# HDR_camera_controller.net
KiCad netlist of a schematic drawn in EAGLE
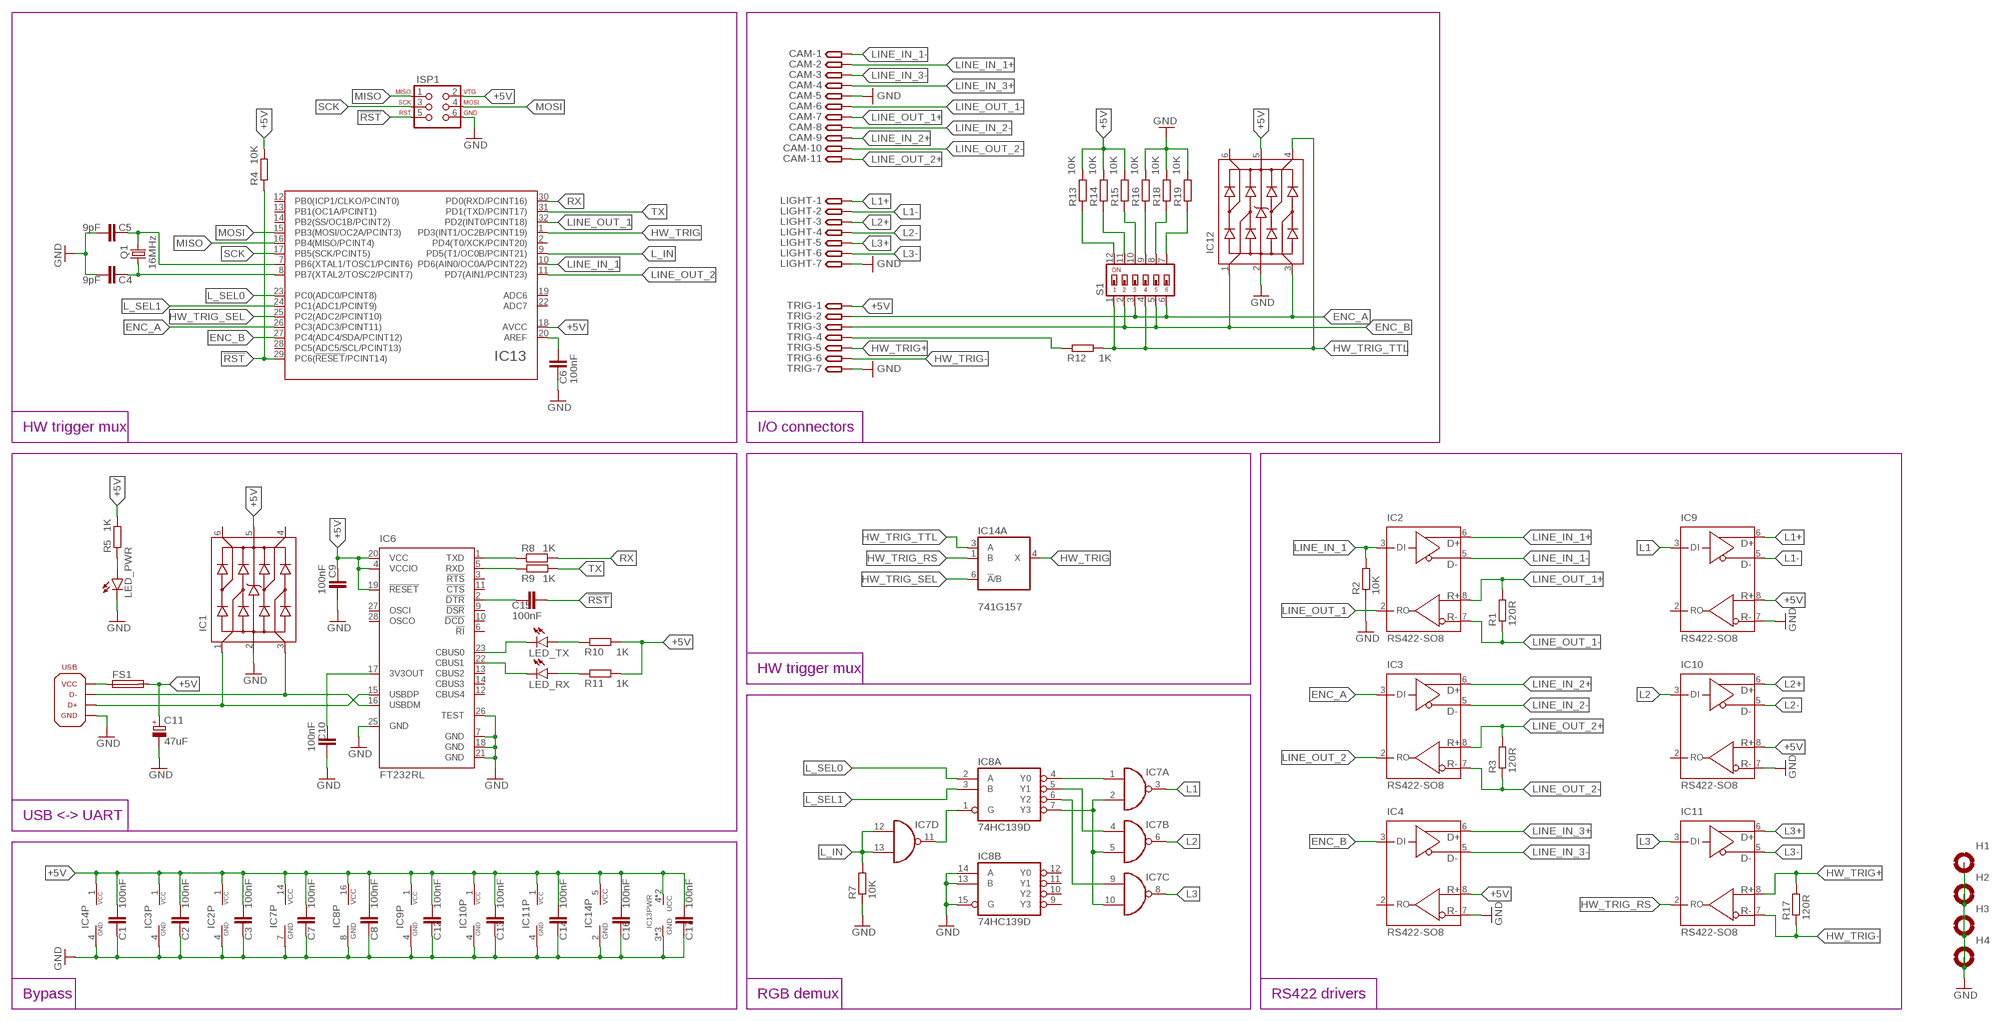
[diagram p0: schematic, sheet 1]

(export (version "E")
  (design (tool "Eeschema 10.0.6"))
  (components
    (comp (ref "C1")
      (value "100nF")
      (footprint "eagle-import:C0805")
      (libsource (lib "eagle-import") (part "C-EUC0805"))
    )
    (comp (ref "C2")
      (value "100nF")
      (footprint "eagle-import:C0805")
      (libsource (lib "eagle-import") (part "C-EUC0805"))
    )
    (comp (ref "C3")
      (value "100nF")
      (footprint "eagle-import:C0805")
      (libsource (lib "eagle-import") (part "C-EUC0805"))
    )
    (comp (ref "C4")
      (value "9pF")
      (footprint "eagle-import:C0805")
      (libsource (lib "eagle-import") (part "C-EUC0805"))
    )
    (comp (ref "C5")
      (value "9pF")
      (footprint "eagle-import:C0805")
      (libsource (lib "eagle-import") (part "C-EUC0805"))
    )
    (comp (ref "C6")
      (value "100nF")
      (footprint "eagle-import:C0805")
      (libsource (lib "eagle-import") (part "C-EUC0805"))
    )
    (comp (ref "C7")
      (value "100nF")
      (footprint "eagle-import:C0805")
      (libsource (lib "eagle-import") (part "C-EUC0805"))
    )
    (comp (ref "C8")
      (value "100nF")
      (footprint "eagle-import:C0805")
      (libsource (lib "eagle-import") (part "C-EUC0805"))
    )
    (comp (ref "C9")
      (value "100nF")
      (footprint "eagle-import:C0805")
      (libsource (lib "eagle-import") (part "C-EUC0805"))
    )
    (comp (ref "C10")
      (value "100nF")
      (footprint "eagle-import:C0805")
      (libsource (lib "eagle-import") (part "C-EUC0805"))
    )
    (comp (ref "C11")
      (value "47uF")
      (footprint "eagle-import:153CLV-0605")
      (fields (field (name "MPN") "SC1E476M6L005VR"))
      (libsource (lib "eagle-import") (part "CPOL-EU153CLV-0605"))
    )
    (comp (ref "C12")
      (value "100nF")
      (footprint "eagle-import:C0805")
      (libsource (lib "eagle-import") (part "C-EUC0805"))
    )
    (comp (ref "C13")
      (value "100nF")
      (footprint "eagle-import:C0805")
      (libsource (lib "eagle-import") (part "C-EUC0805"))
    )
    (comp (ref "C14")
      (value "100nF")
      (footprint "eagle-import:C0805")
      (libsource (lib "eagle-import") (part "C-EUC0805"))
    )
    (comp (ref "C15")
      (value "100nF")
      (footprint "eagle-import:C0805")
      (libsource (lib "eagle-import") (part "C-EUC0805"))
    )
    (comp (ref "C16")
      (value "100nF")
      (footprint "eagle-import:C0805")
      (libsource (lib "eagle-import") (part "C-EUC0805"))
    )
    (comp (ref "C17")
      (value "100nF")
      (footprint "eagle-import:C0805")
      (libsource (lib "eagle-import") (part "C-EUC0805"))
    )
    (comp (ref "CAM")
      (value "SMPAD-11")
      (footprint "eagle-import:S-11P")
      (libsource (lib "eagle-import") (part "SMPAD-11"))
    )
    (comp (ref "FS1")
      (value "POLYFUSE_1210")
      (footprint "eagle-import:1210")
      (fields (field (name "MPN") "SM010-60"))
      (libsource (lib "eagle-import") (part "POLYFUSE_1210"))
    )
    (comp (ref "H1")
      (value "HOLE-3MM_PLATED")
      (footprint "eagle-import:3MM_PLATED")
      (libsource (lib "eagle-import") (part "HOLE-3MM_PLATED"))
    )
    (comp (ref "H2")
      (value "HOLE-3MM_PLATED")
      (footprint "eagle-import:3MM_PLATED")
      (libsource (lib "eagle-import") (part "HOLE-3MM_PLATED"))
    )
    (comp (ref "H3")
      (value "HOLE-3MM_PLATED")
      (footprint "eagle-import:3MM_PLATED")
      (libsource (lib "eagle-import") (part "HOLE-3MM_PLATED"))
    )
    (comp (ref "H4")
      (value "HOLE-3MM_PLATED")
      (footprint "eagle-import:3MM_PLATED")
      (libsource (lib "eagle-import") (part "HOLE-3MM_PLATED"))
    )
    (comp (ref "IC1")
      (value "USBLC6-4")
      (footprint "eagle-import:SOT23-6")
      (fields (field (name "MPN") "USBLC6"))
      (libsource (lib "eagle-import") (part "USBLC6-4"))
    )
    (comp (ref "IC2")
      (value "RS422-SO8")
      (footprint "eagle-import:SO08")
      (fields
        (field (name "MF") "MAXIM")
        (field (name "MPN") "MAX488CSA")
        (field (name "MPN_1") "DS8921AMX/NOPB")
      )
      (libsource (lib "eagle-import") (part "RS422-SO8"))
    )
    (comp (ref "IC3")
      (value "RS422-SO8")
      (footprint "eagle-import:SO08")
      (fields
        (field (name "MF") "MAXIM")
        (field (name "MPN") "MAX488CSA")
        (field (name "MPN_1") "DS8921AMX/NOPB")
      )
      (libsource (lib "eagle-import") (part "RS422-SO8"))
    )
    (comp (ref "IC4")
      (value "RS422-SO8")
      (footprint "eagle-import:SO08")
      (fields
        (field (name "MF") "MAXIM")
        (field (name "MPN") "MAX488CSA")
        (field (name "MPN_1") "DS8921AMX/NOPB")
      )
      (libsource (lib "eagle-import") (part "RS422-SO8"))
    )
    (comp (ref "IC6")
      (value "FT232RL")
      (footprint "eagle-import:SSOP28")
      (libsource (lib "eagle-import") (part "FT232RL"))
    )
    (comp (ref "IC7")
      (value "74HC00D")
      (footprint "eagle-import:SO14")
      (fields (field (name "MPN") "SN74HC00DR"))
      (libsource (lib "eagle-import") (part "7400DHC"))
    )
    (comp (ref "IC8")
      (value "74HC139D")
      (footprint "eagle-import:SO16")
      (fields (field (name "MPN") "SN74HC139DR"))
      (libsource (lib "eagle-import") (part "74139DHC"))
    )
    (comp (ref "IC9")
      (value "RS422-SO8")
      (footprint "eagle-import:SO08")
      (fields
        (field (name "MF") "MAXIM")
        (field (name "MPN") "MAX488CSA")
        (field (name "MPN_1") "DS8921AMX/NOPB")
      )
      (libsource (lib "eagle-import") (part "RS422-SO8"))
    )
    (comp (ref "IC10")
      (value "RS422-SO8")
      (footprint "eagle-import:SO08")
      (fields
        (field (name "MF") "MAXIM")
        (field (name "MPN") "MAX488CSA")
        (field (name "MPN_1") "DS8921AMX/NOPB")
      )
      (libsource (lib "eagle-import") (part "RS422-SO8"))
    )
    (comp (ref "IC11")
      (value "RS422-SO8")
      (footprint "eagle-import:SO08")
      (fields
        (field (name "MF") "MAXIM")
        (field (name "MPN") "MAX488CSA")
        (field (name "MPN_1") "DS8921AMX/NOPB")
      )
      (libsource (lib "eagle-import") (part "RS422-SO8"))
    )
    (comp (ref "IC12")
      (value "USBLC6-4")
      (footprint "eagle-import:SOT23-6")
      (fields (field (name "MPN") "USBLC6"))
      (libsource (lib "eagle-import") (part "USBLC6-4"))
    )
    (comp (ref "IC13")
      (value "ATMEGA48/88/168/328-AU")
      (footprint "eagle-import:TQFP32-08")
      (libsource (lib "eagle-import") (part "ATMEGA48/88/168/328-AU"))
    )
    (comp (ref "IC14")
      (value "741G157")
      (footprint "eagle-import:SOT457W_PHILIPS")
      (fields (field (name "MPN") "74LVC1G157GV.125"))
      (libsource (lib "eagle-import") (part "741G157"))
    )
    (comp (ref "ISP1")
      (value "ISP-SMD")
      (footprint "eagle-import:ISP_SMD")
      (libsource (lib "eagle-import") (part "ISP-SMD"))
    )
    (comp (ref "LED_PWR")
      (value "LEDSML0805")
      (footprint "eagle-import:SML0805")
      (libsource (lib "eagle-import") (part "LEDSML0805"))
    )
    (comp (ref "LED_RX")
      (value "LEDSML0805")
      (footprint "eagle-import:SML0805")
      (libsource (lib "eagle-import") (part "LEDSML0805"))
    )
    (comp (ref "LED_TX")
      (value "LEDSML0805")
      (footprint "eagle-import:SML0805")
      (libsource (lib "eagle-import") (part "LEDSML0805"))
    )
    (comp (ref "LIGHT")
      (value "SMPAD-7")
      (footprint "eagle-import:S-7P")
      (libsource (lib "eagle-import") (part "SMPAD-7"))
    )
    (comp (ref "Q1")
      (value "16MHz")
      (footprint "eagle-import:CRYSTAL-3.2X2.5")
      (fields (field (name "MPN") "3225-16M-SR"))
      (libsource (lib "eagle-import") (part "RESONATOR_CRY"))
    )
    (comp (ref "R1")
      (value "120R")
      (footprint "eagle-import:R0805")
      (libsource (lib "eagle-import") (part "R-EU_R0805"))
    )
    (comp (ref "R2")
      (value "10K")
      (footprint "eagle-import:R0805")
      (libsource (lib "eagle-import") (part "R-EU_R0805"))
    )
    (comp (ref "R3")
      (value "120R")
      (footprint "eagle-import:R0805")
      (libsource (lib "eagle-import") (part "R-EU_R0805"))
    )
    (comp (ref "R4")
      (value "10K")
      (footprint "eagle-import:R0805")
      (libsource (lib "eagle-import") (part "R-EU_R0805"))
    )
    (comp (ref "R5")
      (value "1K")
      (footprint "eagle-import:R0805")
      (libsource (lib "eagle-import") (part "R-EU_R0805"))
    )
    (comp (ref "R7")
      (value "10K")
      (footprint "eagle-import:R0805")
      (libsource (lib "eagle-import") (part "R-EU_R0805"))
    )
    (comp (ref "R8")
      (value "1K")
      (footprint "eagle-import:R0805")
      (libsource (lib "eagle-import") (part "R-EU_R0805"))
    )
    (comp (ref "R9")
      (value "1K")
      (footprint "eagle-import:R0805")
      (libsource (lib "eagle-import") (part "R-EU_R0805"))
    )
    (comp (ref "R10")
      (value "1K")
      (footprint "eagle-import:R0805")
      (libsource (lib "eagle-import") (part "R-EU_R0805"))
    )
    (comp (ref "R11")
      (value "1K")
      (footprint "eagle-import:R0805")
      (libsource (lib "eagle-import") (part "R-EU_R0805"))
    )
    (comp (ref "R12")
      (value "1K")
      (footprint "eagle-import:R0805")
      (libsource (lib "eagle-import") (part "R-EU_R0805"))
    )
    (comp (ref "R13")
      (value "10K")
      (footprint "eagle-import:R0805")
      (libsource (lib "eagle-import") (part "R-EU_R0805"))
    )
    (comp (ref "R14")
      (value "10K")
      (footprint "eagle-import:R0805")
      (libsource (lib "eagle-import") (part "R-EU_R0805"))
    )
    (comp (ref "R15")
      (value "10K")
      (footprint "eagle-import:R0805")
      (libsource (lib "eagle-import") (part "R-EU_R0805"))
    )
    (comp (ref "R16")
      (value "10K")
      (footprint "eagle-import:R0805")
      (libsource (lib "eagle-import") (part "R-EU_R0805"))
    )
    (comp (ref "R17")
      (value "120R")
      (footprint "eagle-import:R0805")
      (libsource (lib "eagle-import") (part "R-EU_R0805"))
    )
    (comp (ref "R18")
      (value "10K")
      (footprint "eagle-import:R0805")
      (libsource (lib "eagle-import") (part "R-EU_R0805"))
    )
    (comp (ref "R19")
      (value "10K")
      (footprint "eagle-import:R0805")
      (libsource (lib "eagle-import") (part "R-EU_R0805"))
    )
    (comp (ref "S1")
      (value "SWS006")
      (footprint "eagle-import:SMS-006")
      (fields (field (name "MPN") "A6S-6102-H"))
      (libsource (lib "eagle-import") (part "SWS006"))
    )
    (comp (ref "TRIG")
      (value "SMPAD-7")
      (footprint "eagle-import:S-7P")
      (libsource (lib "eagle-import") (part "SMPAD-7"))
    )
    (comp (ref "USB")
      (value "USB_AB-B_SMD")
      (footprint "eagle-import:USB_B_SMD")
      (fields (field (name "MPN") "USBB-G-SMD"))
      (libsource (lib "eagle-import") (part "USB_AB-B_SMD"))
    )
  )
  (nets
    (net (code "1") (name "+5V") (class "Default")
      (node (ref "C1") (pin "1") (pinfunction "1_1") (pintype "passive"))
      (node (ref "C11") (pin "+") (pinfunction "+_+") (pintype "passive"))
      (node (ref "C12") (pin "1") (pinfunction "1_1") (pintype "passive"))
      (node (ref "C13") (pin "1") (pinfunction "1_1") (pintype "passive"))
      (node (ref "C14") (pin "1") (pinfunction "1_1") (pintype "passive"))
      (node (ref "C16") (pin "1") (pinfunction "1_1") (pintype "passive"))
      (node (ref "C17") (pin "1") (pinfunction "1_1") (pintype "passive"))
      (node (ref "C2") (pin "1") (pinfunction "1_1") (pintype "passive"))
      (node (ref "C3") (pin "1") (pinfunction "1_1") (pintype "passive"))
      (node (ref "C7") (pin "1") (pinfunction "1_1") (pintype "passive"))
      (node (ref "C8") (pin "1") (pinfunction "1_1") (pintype "passive"))
      (node (ref "C9") (pin "2") (pinfunction "2_2") (pintype "passive"))
      (node (ref "FS1") (pin "2") (pinfunction "2_2") (pintype "passive"))
      (node (ref "IC1") (pin "5") (pinfunction "P$5_5") (pintype "bidirectional"))
      (node (ref "IC10") (pin "1") (pinfunction "VCC_1") (pintype "power_in"))
      (node (ref "IC10") (pin "8") (pinfunction "R+_8") (pintype "input"))
      (node (ref "IC11") (pin "1") (pinfunction "VCC_1") (pintype "power_in"))
      (node (ref "IC12") (pin "5") (pinfunction "P$5_5") (pintype "bidirectional"))
      (node (ref "IC13") (pin "18") (pinfunction "AVCC_18") (pintype "power_in"))
      (node (ref "IC13") (pin "4") (pinfunction "UCC_4") (pintype "power_in"))
      (node (ref "IC13") (pin "6") (pinfunction "UCC_6") (pintype "power_in"))
      (node (ref "IC14") (pin "5") (pinfunction "VCC_5") (pintype "power_in"))
      (node (ref "IC2") (pin "1") (pinfunction "VCC_1") (pintype "power_in"))
      (node (ref "IC3") (pin "1") (pinfunction "VCC_1") (pintype "power_in"))
      (node (ref "IC4") (pin "1") (pinfunction "VCC_1") (pintype "power_in"))
      (node (ref "IC4") (pin "8") (pinfunction "R+_8") (pintype "input"))
      (node (ref "IC6") (pin "19") (pinfunction "~{RESET}_19") (pintype "input"))
      (node (ref "IC6") (pin "20") (pinfunction "VCC_20") (pintype "power_in"))
      (node (ref "IC6") (pin "4") (pinfunction "VCCIO_4") (pintype "power_in"))
      (node (ref "IC7") (pin "14") (pinfunction "VCC_14") (pintype "power_in"))
      (node (ref "IC8") (pin "16") (pinfunction "VCC_16") (pintype "power_in"))
      (node (ref "IC9") (pin "1") (pinfunction "VCC_1") (pintype "power_in"))
      (node (ref "IC9") (pin "8") (pinfunction "R+_8") (pintype "input"))
      (node (ref "ISP1") (pin "2") (pinfunction "VTG_2") (pintype "passive"))
      (node (ref "R10") (pin "2") (pinfunction "2_2") (pintype "passive"))
      (node (ref "R11") (pin "2") (pinfunction "2_2") (pintype "passive"))
      (node (ref "R13") (pin "2") (pinfunction "2_2") (pintype "passive"))
      (node (ref "R14") (pin "2") (pinfunction "2_2") (pintype "passive"))
      (node (ref "R15") (pin "2") (pinfunction "2_2") (pintype "passive"))
      (node (ref "R4") (pin "2") (pinfunction "2_2") (pintype "passive"))
      (node (ref "R5") (pin "2") (pinfunction "2_2") (pintype "passive"))
      (node (ref "TRIG") (pin "1") (pinfunction "P_1") (pintype "passive"))
    )
    (net (code "2") (name "/~{RST}") (class "Default")
      (node (ref "C15") (pin "1") (pinfunction "1_1") (pintype "passive"))
      (node (ref "IC13") (pin "29") (pinfunction "PC6(~{RESET}/PCINT14)_29") (pintype "bidirectional"))
      (node (ref "ISP1") (pin "5") (pinfunction "RST_5") (pintype "passive"))
      (node (ref "R4") (pin "1") (pinfunction "1_1") (pintype "passive"))
    )
    (net (code "3") (name "ENC_A") (class "Default")
      (node (ref "IC12") (pin "3") (pinfunction "P$3_3") (pintype "bidirectional"))
      (node (ref "IC13") (pin "26") (pinfunction "PC3(ADC3/PCINT11)_26") (pintype "bidirectional"))
      (node (ref "IC3") (pin "3") (pinfunction "DI_3") (pintype "input"))
      (node (ref "S1") (pin "3") (pinfunction "3_3") (pintype "passive"))
      (node (ref "S1") (pin "6") (pinfunction "6_6") (pintype "passive"))
      (node (ref "TRIG") (pin "2") (pinfunction "P_2") (pintype "passive"))
    )
    (net (code "4") (name "ENC_B") (class "Default")
      (node (ref "IC12") (pin "1") (pinfunction "P$1_1") (pintype "bidirectional"))
      (node (ref "IC13") (pin "27") (pinfunction "PC4(ADC4/SDA/PCINT12)_27") (pintype "bidirectional"))
      (node (ref "IC4") (pin "3") (pinfunction "DI_3") (pintype "input"))
      (node (ref "S1") (pin "2") (pinfunction "2_2") (pintype "passive"))
      (node (ref "S1") (pin "5") (pinfunction "5_5") (pintype "passive"))
      (node (ref "TRIG") (pin "3") (pinfunction "P_3") (pintype "passive"))
    )
    (net (code "5") (name "GND") (class "Default")
      (node (ref "C1") (pin "2") (pinfunction "2_2") (pintype "passive"))
      (node (ref "C10") (pin "1") (pinfunction "1_1") (pintype "passive"))
      (node (ref "C11") (pin "-") (pinfunction "-_-") (pintype "passive"))
      (node (ref "C12") (pin "2") (pinfunction "2_2") (pintype "passive"))
      (node (ref "C13") (pin "2") (pinfunction "2_2") (pintype "passive"))
      (node (ref "C14") (pin "2") (pinfunction "2_2") (pintype "passive"))
      (node (ref "C16") (pin "2") (pinfunction "2_2") (pintype "passive"))
      (node (ref "C17") (pin "2") (pinfunction "2_2") (pintype "passive"))
      (node (ref "C2") (pin "2") (pinfunction "2_2") (pintype "passive"))
      (node (ref "C3") (pin "2") (pinfunction "2_2") (pintype "passive"))
      (node (ref "C4") (pin "1") (pinfunction "1_1") (pintype "passive"))
      (node (ref "C5") (pin "1") (pinfunction "1_1") (pintype "passive"))
      (node (ref "C6") (pin "2") (pinfunction "2_2") (pintype "passive"))
      (node (ref "C7") (pin "2") (pinfunction "2_2") (pintype "passive"))
      (node (ref "C8") (pin "2") (pinfunction "2_2") (pintype "passive"))
      (node (ref "C9") (pin "1") (pinfunction "1_1") (pintype "passive"))
      (node (ref "CAM") (pin "5") (pinfunction "P_5") (pintype "passive"))
      (node (ref "H1") (pin "1") (pinfunction "MOUNT_1") (pintype "passive"))
      (node (ref "H2") (pin "1") (pinfunction "MOUNT_1") (pintype "passive"))
      (node (ref "H3") (pin "1") (pinfunction "MOUNT_1") (pintype "passive"))
      (node (ref "H4") (pin "1") (pinfunction "MOUNT_1") (pintype "passive"))
      (node (ref "IC1") (pin "2") (pinfunction "P$2_2") (pintype "bidirectional"))
      (node (ref "IC10") (pin "4") (pinfunction "GND_4") (pintype "power_in"))
      (node (ref "IC10") (pin "7") (pinfunction "R-_7") (pintype "input"))
      (node (ref "IC11") (pin "4") (pinfunction "GND_4") (pintype "power_in"))
      (node (ref "IC12") (pin "2") (pinfunction "P$2_2") (pintype "bidirectional"))
      (node (ref "IC13") (pin "21") (pinfunction "GND_21") (pintype "power_in"))
      (node (ref "IC13") (pin "3") (pinfunction "GND_3") (pintype "power_in"))
      (node (ref "IC13") (pin "5") (pinfunction "GND_5") (pintype "power_in"))
      (node (ref "IC14") (pin "2") (pinfunction "GND_2") (pintype "power_in"))
      (node (ref "IC2") (pin "4") (pinfunction "GND_4") (pintype "power_in"))
      (node (ref "IC3") (pin "4") (pinfunction "GND_4") (pintype "power_in"))
      (node (ref "IC4") (pin "4") (pinfunction "GND_4") (pintype "power_in"))
      (node (ref "IC4") (pin "7") (pinfunction "R-_7") (pintype "input"))
      (node (ref "IC6") (pin "18") (pinfunction "GND_18") (pintype "power_in"))
      (node (ref "IC6") (pin "21") (pinfunction "GND_21") (pintype "power_in"))
      (node (ref "IC6") (pin "25") (pinfunction "GND_25") (pintype "power_in"))
      (node (ref "IC6") (pin "26") (pinfunction "TEST_26") (pintype "input"))
      (node (ref "IC6") (pin "7") (pinfunction "GND_7") (pintype "power_in"))
      (node (ref "IC7") (pin "7") (pinfunction "GND_7") (pintype "power_in"))
      (node (ref "IC8") (pin "13") (pinfunction "B_13") (pintype "input"))
      (node (ref "IC8") (pin "14") (pinfunction "A_14") (pintype "input"))
      (node (ref "IC8") (pin "15") (pinfunction "G_15") (pintype "input"))
      (node (ref "IC8") (pin "8") (pinfunction "GND_8") (pintype "power_in"))
      (node (ref "IC9") (pin "4") (pinfunction "GND_4") (pintype "power_in"))
      (node (ref "IC9") (pin "7") (pinfunction "R-_7") (pintype "input"))
      (node (ref "ISP1") (pin "6") (pinfunction "GND_6") (pintype "passive"))
      (node (ref "LED_PWR") (pin "C") (pinfunction "C_C") (pintype "passive"))
      (node (ref "LIGHT") (pin "7") (pinfunction "P_7") (pintype "passive"))
      (node (ref "R16") (pin "2") (pinfunction "2_2") (pintype "passive"))
      (node (ref "R18") (pin "2") (pinfunction "2_2") (pintype "passive"))
      (node (ref "R19") (pin "2") (pinfunction "2_2") (pintype "passive"))
      (node (ref "R2") (pin "1") (pinfunction "1_1") (pintype "passive"))
      (node (ref "R7") (pin "1") (pinfunction "1_1") (pintype "passive"))
      (node (ref "TRIG") (pin "7") (pinfunction "P_7") (pintype "passive"))
      (node (ref "USB") (pin "4") (pinfunction "GND_4") (pintype "bidirectional"))
      (node (ref "USB") (pin "G1") (pinfunction "GND_G1") (pintype "bidirectional"))
      (node (ref "USB") (pin "G2") (pinfunction "GND_G2") (pintype "bidirectional"))
    )
    (net (code "6") (name "HW_TRIG") (class "Default")
      (node (ref "IC13") (pin "1") (pinfunction "PD3(INT1/OC2B/PCINT19)_1") (pintype "bidirectional"))
      (node (ref "IC14") (pin "4") (pinfunction "X_4") (pintype "bidirectional"))
    )
    (net (code "7") (name "HW_TRIG+") (class "Default")
      (node (ref "IC11") (pin "8") (pinfunction "R+_8") (pintype "input"))
      (node (ref "R17") (pin "2") (pinfunction "2_2") (pintype "passive"))
      (node (ref "TRIG") (pin "5") (pinfunction "P_5") (pintype "passive"))
    )
    (net (code "8") (name "HW_TRIG-") (class "Default")
      (node (ref "IC11") (pin "7") (pinfunction "R-_7") (pintype "input"))
      (node (ref "R17") (pin "1") (pinfunction "1_1") (pintype "passive"))
      (node (ref "TRIG") (pin "6") (pinfunction "P_6") (pintype "passive"))
    )
    (net (code "9") (name "HW_TRIG_RS") (class "Default")
      (node (ref "IC11") (pin "2") (pinfunction "RO_2") (pintype "output"))
      (node (ref "IC14") (pin "1") (pinfunction "B_1") (pintype "bidirectional"))
    )
    (net (code "10") (name "HW_TRIG_SEL") (class "Default")
      (node (ref "IC13") (pin "25") (pinfunction "PC2(ADC2/PCINT10)_25") (pintype "bidirectional"))
      (node (ref "IC14") (pin "6") (pinfunction "~{A}/B_6") (pintype "input"))
    )
    (net (code "11") (name "HW_TRIG_TTL") (class "Default")
      (node (ref "IC12") (pin "4") (pinfunction "P$4_4") (pintype "bidirectional"))
      (node (ref "IC14") (pin "3") (pinfunction "A_3") (pintype "bidirectional"))
      (node (ref "R12") (pin "2") (pinfunction "2_2") (pintype "passive"))
      (node (ref "S1") (pin "1") (pinfunction "1_1") (pintype "passive"))
      (node (ref "S1") (pin "4") (pinfunction "4_4") (pintype "passive"))
    )
    (net (code "12") (name "L1") (class "Default")
      (node (ref "IC7") (pin "3") (pinfunction "O_3") (pintype "output"))
      (node (ref "IC9") (pin "3") (pinfunction "DI_3") (pintype "input"))
    )
    (net (code "13") (name "L1+") (class "Default")
      (node (ref "IC9") (pin "6") (pinfunction "D+_6") (pintype "output"))
      (node (ref "LIGHT") (pin "1") (pinfunction "P_1") (pintype "passive"))
    )
    (net (code "14") (name "L1-") (class "Default")
      (node (ref "IC9") (pin "5") (pinfunction "D-_5") (pintype "output"))
      (node (ref "LIGHT") (pin "2") (pinfunction "P_2") (pintype "passive"))
    )
    (net (code "15") (name "L2") (class "Default")
      (node (ref "IC10") (pin "3") (pinfunction "DI_3") (pintype "input"))
      (node (ref "IC7") (pin "6") (pinfunction "O_6") (pintype "output"))
    )
    (net (code "16") (name "L2+") (class "Default")
      (node (ref "IC10") (pin "6") (pinfunction "D+_6") (pintype "output"))
      (node (ref "LIGHT") (pin "3") (pinfunction "P_3") (pintype "passive"))
    )
    (net (code "17") (name "L2-") (class "Default")
      (node (ref "IC10") (pin "5") (pinfunction "D-_5") (pintype "output"))
      (node (ref "LIGHT") (pin "4") (pinfunction "P_4") (pintype "passive"))
    )
    (net (code "18") (name "L3") (class "Default")
      (node (ref "IC11") (pin "3") (pinfunction "DI_3") (pintype "input"))
      (node (ref "IC7") (pin "8") (pinfunction "O_8") (pintype "output"))
    )
    (net (code "19") (name "L3+") (class "Default")
      (node (ref "IC11") (pin "6") (pinfunction "D+_6") (pintype "output"))
      (node (ref "LIGHT") (pin "5") (pinfunction "P_5") (pintype "passive"))
    )
    (net (code "20") (name "L3-") (class "Default")
      (node (ref "IC11") (pin "5") (pinfunction "D-_5") (pintype "output"))
      (node (ref "LIGHT") (pin "6") (pinfunction "P_6") (pintype "passive"))
    )
    (net (code "21") (name "LINE_IN_1") (class "Default")
      (node (ref "IC13") (pin "10") (pinfunction "PD6(AIN0/OC0A/PCINT22)_10") (pintype "bidirectional"))
      (node (ref "IC2") (pin "3") (pinfunction "DI_3") (pintype "input"))
      (node (ref "R2") (pin "2") (pinfunction "2_2") (pintype "passive"))
    )
    (net (code "22") (name "LINE_IN_1+") (class "Default")
      (node (ref "CAM") (pin "2") (pinfunction "P_2") (pintype "passive"))
      (node (ref "IC2") (pin "6") (pinfunction "D+_6") (pintype "output"))
    )
    (net (code "23") (name "LINE_IN_1-") (class "Default")
      (node (ref "CAM") (pin "1") (pinfunction "P_1") (pintype "passive"))
      (node (ref "IC2") (pin "5") (pinfunction "D-_5") (pintype "output"))
    )
    (net (code "24") (name "LINE_IN_2+") (class "Default")
      (node (ref "CAM") (pin "9") (pinfunction "P_9") (pintype "passive"))
      (node (ref "IC3") (pin "6") (pinfunction "D+_6") (pintype "output"))
    )
    (net (code "25") (name "LINE_IN_2-") (class "Default")
      (node (ref "CAM") (pin "8") (pinfunction "P_8") (pintype "passive"))
      (node (ref "IC3") (pin "5") (pinfunction "D-_5") (pintype "output"))
    )
    (net (code "26") (name "LINE_IN_3+") (class "Default")
      (node (ref "CAM") (pin "4") (pinfunction "P_4") (pintype "passive"))
      (node (ref "IC4") (pin "6") (pinfunction "D+_6") (pintype "output"))
    )
    (net (code "27") (name "LINE_IN_3-") (class "Default")
      (node (ref "CAM") (pin "3") (pinfunction "P_3") (pintype "passive"))
      (node (ref "IC4") (pin "5") (pinfunction "D-_5") (pintype "output"))
    )
    (net (code "28") (name "LINE_OUT_1") (class "Default")
      (node (ref "IC13") (pin "32") (pinfunction "PD2(INT0/PCINT18)_32") (pintype "bidirectional"))
      (node (ref "IC2") (pin "2") (pinfunction "RO_2") (pintype "output"))
    )
    (net (code "29") (name "LINE_OUT_1+") (class "Default")
      (node (ref "CAM") (pin "7") (pinfunction "P_7") (pintype "passive"))
      (node (ref "IC2") (pin "8") (pinfunction "R+_8") (pintype "input"))
      (node (ref "R1") (pin "2") (pinfunction "2_2") (pintype "passive"))
    )
    (net (code "30") (name "LINE_OUT_1-") (class "Default")
      (node (ref "CAM") (pin "6") (pinfunction "P_6") (pintype "passive"))
      (node (ref "IC2") (pin "7") (pinfunction "R-_7") (pintype "input"))
      (node (ref "R1") (pin "1") (pinfunction "1_1") (pintype "passive"))
    )
    (net (code "31") (name "LINE_OUT_2") (class "Default")
      (node (ref "IC13") (pin "11") (pinfunction "PD7(AIN1/PCINT23)_11") (pintype "bidirectional"))
      (node (ref "IC3") (pin "2") (pinfunction "RO_2") (pintype "output"))
    )
    (net (code "32") (name "LINE_OUT_2+") (class "Default")
      (node (ref "CAM") (pin "11") (pinfunction "P_11") (pintype "passive"))
      (node (ref "IC3") (pin "8") (pinfunction "R+_8") (pintype "input"))
      (node (ref "R3") (pin "2") (pinfunction "2_2") (pintype "passive"))
    )
    (net (code "33") (name "LINE_OUT_2-") (class "Default")
      (node (ref "CAM") (pin "10") (pinfunction "P_10") (pintype "passive"))
      (node (ref "IC3") (pin "7") (pinfunction "R-_7") (pintype "input"))
      (node (ref "R3") (pin "1") (pinfunction "1_1") (pintype "passive"))
    )
    (net (code "34") (name "L_IN") (class "Default")
      (node (ref "IC13") (pin "9") (pinfunction "PD5(T1/OC0B/PCINT21)_9") (pintype "bidirectional"))
      (node (ref "IC7") (pin "12") (pinfunction "I0_12") (pintype "input"))
      (node (ref "IC7") (pin "13") (pinfunction "I1_13") (pintype "input"))
      (node (ref "R7") (pin "2") (pinfunction "2_2") (pintype "passive"))
    )
    (net (code "35") (name "L_SEL0") (class "Default")
      (node (ref "IC13") (pin "23") (pinfunction "PC0(ADC0/PCINT8)_23") (pintype "bidirectional"))
      (node (ref "IC8") (pin "2") (pinfunction "A_2") (pintype "input"))
    )
    (net (code "36") (name "L_SEL1") (class "Default")
      (node (ref "IC13") (pin "24") (pinfunction "PC1(ADC1/PCINT9)_24") (pintype "bidirectional"))
      (node (ref "IC8") (pin "3") (pinfunction "B_3") (pintype "input"))
    )
    (net (code "37") (name "MISO") (class "Default")
      (node (ref "IC13") (pin "16") (pinfunction "PB4(MISO/PCINT4)_16") (pintype "bidirectional"))
      (node (ref "ISP1") (pin "1") (pinfunction "MISO_1") (pintype "passive"))
    )
    (net (code "38") (name "MOSI") (class "Default")
      (node (ref "IC13") (pin "15") (pinfunction "PB3(MOSI/OC2A/PCINT3)_15") (pintype "bidirectional"))
      (node (ref "ISP1") (pin "4") (pinfunction "MOSI_4") (pintype "passive"))
    )
    (net (code "39") (name "Net-(IC1-P$1)") (class "Default")
      (node (ref "IC1") (pin "1") (pinfunction "P$1_1") (pintype "bidirectional"))
      (node (ref "IC6") (pin "15") (pinfunction "USBDP_15") (pintype "bidirectional"))
      (node (ref "USB") (pin "3") (pinfunction "D+_3") (pintype "bidirectional"))
    )
    (net (code "40") (name "Net-(IC1-P$3)") (class "Default")
      (node (ref "IC1") (pin "3") (pinfunction "P$3_3") (pintype "bidirectional"))
      (node (ref "IC6") (pin "16") (pinfunction "USBDM_16") (pintype "bidirectional"))
      (node (ref "USB") (pin "2") (pinfunction "D-_2") (pintype "bidirectional"))
    )
    (net (code "41") (name "Net-(IC6-3V3OUT)") (class "Default")
      (node (ref "C10") (pin "2") (pinfunction "2_2") (pintype "passive"))
      (node (ref "IC6") (pin "17") (pinfunction "3V3OUT_17") (pintype "output"))
    )
    (net (code "42") (name "Net-(IC6-CBUS0)") (class "Default")
      (node (ref "IC6") (pin "23") (pinfunction "CBUS0_23") (pintype "bidirectional"))
      (node (ref "LED_TX") (pin "C") (pinfunction "C_C") (pintype "passive"))
    )
    (net (code "43") (name "Net-(IC6-CBUS1)") (class "Default")
      (node (ref "IC6") (pin "22") (pinfunction "CBUS1_22") (pintype "bidirectional"))
      (node (ref "LED_RX") (pin "C") (pinfunction "C_C") (pintype "passive"))
    )
    (net (code "44") (name "Net-(IC6-RXD)") (class "Default")
      (node (ref "IC6") (pin "5") (pinfunction "RXD_5") (pintype "input"))
      (node (ref "R9") (pin "1") (pinfunction "1_1") (pintype "passive"))
    )
    (net (code "45") (name "Net-(IC6-TXD)") (class "Default")
      (node (ref "IC6") (pin "1") (pinfunction "TXD_1") (pintype "output"))
      (node (ref "R8") (pin "1") (pinfunction "1_1") (pintype "passive"))
    )
    (net (code "46") (name "Net-(IC6-~{DTR})") (class "Default")
      (node (ref "C15") (pin "2") (pinfunction "2_2") (pintype "passive"))
      (node (ref "IC6") (pin "2") (pinfunction "~{DTR}_2") (pintype "output"))
    )
    (net (code "47") (name "Net-(IC7A-I0)") (class "Default")
      (node (ref "IC7") (pin "1") (pinfunction "I0_1") (pintype "input"))
      (node (ref "IC8") (pin "4") (pinfunction "Y0_4") (pintype "output"))
    )
    (net (code "48") (name "Net-(IC7A-I1)") (class "Default")
      (node (ref "IC7") (pin "10") (pinfunction "I1_10") (pintype "input"))
      (node (ref "IC7") (pin "2") (pinfunction "I1_2") (pintype "input"))
      (node (ref "IC7") (pin "5") (pinfunction "I1_5") (pintype "input"))
      (node (ref "IC8") (pin "7") (pinfunction "Y3_7") (pintype "output"))
    )
    (net (code "49") (name "Net-(IC7B-I0)") (class "Default")
      (node (ref "IC7") (pin "4") (pinfunction "I0_4") (pintype "input"))
      (node (ref "IC8") (pin "5") (pinfunction "Y1_5") (pintype "output"))
    )
    (net (code "50") (name "Net-(IC7C-I0)") (class "Default")
      (node (ref "IC7") (pin "9") (pinfunction "I0_9") (pintype "input"))
      (node (ref "IC8") (pin "6") (pinfunction "Y2_6") (pintype "output"))
    )
    (net (code "51") (name "Net-(IC7D-O)") (class "Default")
      (node (ref "IC7") (pin "11") (pinfunction "O_11") (pintype "output"))
      (node (ref "IC8") (pin "1") (pinfunction "G_1") (pintype "input"))
    )
    (net (code "52") (name "Net-(IC13A-AREF)") (class "Default")
      (node (ref "C6") (pin "1") (pinfunction "1_1") (pintype "passive"))
      (node (ref "IC13") (pin "20") (pinfunction "AREF_20") (pintype "passive"))
    )
    (net (code "53") (name "Net-(IC13A-PB6(XTAL1{slash}TOSC1{slash}PCINT6))") (class "Default")
      (node (ref "C5") (pin "2") (pinfunction "2_2") (pintype "passive"))
      (node (ref "IC13") (pin "7") (pinfunction "PB6(XTAL1/TOSC1/PCINT6)_7") (pintype "bidirectional"))
      (node (ref "Q1") (pin "3") (pinfunction "2_3") (pintype "passive"))
    )
    (net (code "54") (name "Net-(IC13A-PB7(XTAL2{slash}TOSC2{slash}PCINT7))") (class "Default")
      (node (ref "C4") (pin "2") (pinfunction "2_2") (pintype "passive"))
      (node (ref "IC13") (pin "8") (pinfunction "PB7(XTAL2/TOSC2/PCINT7)_8") (pintype "bidirectional"))
      (node (ref "Q1") (pin "1") (pinfunction "1_1") (pintype "passive"))
    )
    (net (code "55") (name "Net-(LED_PWR-PadA)") (class "Default")
      (node (ref "LED_PWR") (pin "A") (pinfunction "A_A") (pintype "passive"))
      (node (ref "R5") (pin "1") (pinfunction "1_1") (pintype "passive"))
    )
    (net (code "56") (name "Net-(LED_RX-PadA)") (class "Default")
      (node (ref "LED_RX") (pin "A") (pinfunction "A_A") (pintype "passive"))
      (node (ref "R11") (pin "1") (pinfunction "1_1") (pintype "passive"))
    )
    (net (code "57") (name "Net-(LED_TX-PadA)") (class "Default")
      (node (ref "LED_TX") (pin "A") (pinfunction "A_A") (pintype "passive"))
      (node (ref "R10") (pin "1") (pinfunction "1_1") (pintype "passive"))
    )
    (net (code "58") (name "Net-(R13-Pad1)") (class "Default")
      (node (ref "R13") (pin "1") (pinfunction "1_1") (pintype "passive"))
      (node (ref "S1") (pin "12") (pinfunction "12_12") (pintype "passive"))
    )
    (net (code "59") (name "Net-(R14-Pad1)") (class "Default")
      (node (ref "R14") (pin "1") (pinfunction "1_1") (pintype "passive"))
      (node (ref "S1") (pin "11") (pinfunction "11_11") (pintype "passive"))
    )
    (net (code "60") (name "Net-(R15-Pad1)") (class "Default")
      (node (ref "R15") (pin "1") (pinfunction "1_1") (pintype "passive"))
      (node (ref "S1") (pin "10") (pinfunction "10_10") (pintype "passive"))
    )
    (net (code "61") (name "Net-(R16-Pad1)") (class "Default")
      (node (ref "R16") (pin "1") (pinfunction "1_1") (pintype "passive"))
      (node (ref "S1") (pin "9") (pinfunction "9_9") (pintype "passive"))
    )
    (net (code "62") (name "Net-(R18-Pad1)") (class "Default")
      (node (ref "R18") (pin "1") (pinfunction "1_1") (pintype "passive"))
      (node (ref "S1") (pin "8") (pinfunction "8_8") (pintype "passive"))
    )
    (net (code "63") (name "Net-(R19-Pad1)") (class "Default")
      (node (ref "R19") (pin "1") (pinfunction "1_1") (pintype "passive"))
      (node (ref "S1") (pin "7") (pinfunction "7_7") (pintype "passive"))
    )
    (net (code "64") (name "Net-(TRIGD-P)") (class "Default")
      (node (ref "R12") (pin "1") (pinfunction "1_1") (pintype "passive"))
      (node (ref "TRIG") (pin "4") (pinfunction "P_4") (pintype "passive"))
    )
    (net (code "65") (name "Net-(USB-VCC)") (class "Default")
      (node (ref "FS1") (pin "1") (pinfunction "1_1") (pintype "passive"))
      (node (ref "USB") (pin "1") (pinfunction "VCC_1") (pintype "bidirectional"))
    )
    (net (code "66") (name "RX") (class "Default")
      (node (ref "IC13") (pin "30") (pinfunction "PD0(RXD/PCINT16)_30") (pintype "bidirectional"))
      (node (ref "R8") (pin "2") (pinfunction "2_2") (pintype "passive"))
    )
    (net (code "67") (name "SCK") (class "Default")
      (node (ref "IC13") (pin "17") (pinfunction "PB5(SCK/PCINT5)_17") (pintype "bidirectional"))
      (node (ref "ISP1") (pin "3") (pinfunction "SCK_3") (pintype "passive"))
    )
    (net (code "68") (name "TX") (class "Default")
      (node (ref "IC13") (pin "31") (pinfunction "PD1(TXD/PCINT17)_31") (pintype "bidirectional"))
      (node (ref "R9") (pin "2") (pinfunction "2_2") (pintype "passive"))
    )
    (net (code "69") (name "unconnected-(IC1-P$4-Pad4)") (class "Default")
      (node (ref "IC1") (pin "4") (pinfunction "P$4_4") (pintype "bidirectional"))
    )
    (net (code "70") (name "unconnected-(IC1-P$6-Pad6)") (class "Default")
      (node (ref "IC1") (pin "6") (pinfunction "P$6_6") (pintype "bidirectional"))
    )
    (net (code "71") (name "unconnected-(IC4A-RO-Pad2)") (class "Default")
      (node (ref "IC4") (pin "2") (pinfunction "RO_2") (pintype "output"))
    )
    (net (code "72") (name "unconnected-(IC6-CBUS2-Pad13)") (class "Default")
      (node (ref "IC6") (pin "13") (pinfunction "CBUS2_13") (pintype "bidirectional"))
    )
    (net (code "73") (name "unconnected-(IC6-CBUS3-Pad14)") (class "Default")
      (node (ref "IC6") (pin "14") (pinfunction "CBUS3_14") (pintype "bidirectional"))
    )
    (net (code "74") (name "unconnected-(IC6-CBUS4-Pad12)") (class "Default")
      (node (ref "IC6") (pin "12") (pinfunction "CBUS4_12") (pintype "bidirectional"))
    )
    (net (code "75") (name "unconnected-(IC6-OSCI-Pad27)") (class "Default")
      (node (ref "IC6") (pin "27") (pinfunction "OSCI_27") (pintype "input"))
    )
    (net (code "76") (name "unconnected-(IC6-OSCO-Pad28)") (class "Default")
      (node (ref "IC6") (pin "28") (pinfunction "OSCO_28") (pintype "output"))
    )
    (net (code "77") (name "unconnected-(IC6-~{CTS}-Pad11)") (class "Default")
      (node (ref "IC6") (pin "11") (pinfunction "~{CTS}_11") (pintype "input"))
    )
    (net (code "78") (name "unconnected-(IC6-~{DCD}-Pad10)") (class "Default")
      (node (ref "IC6") (pin "10") (pinfunction "~{DCD}_10") (pintype "input"))
    )
    (net (code "79") (name "unconnected-(IC6-~{DSR}-Pad9)") (class "Default")
      (node (ref "IC6") (pin "9") (pinfunction "~{DSR}_9") (pintype "input"))
    )
    (net (code "80") (name "unconnected-(IC6-~{RI}-Pad6)") (class "Default")
      (node (ref "IC6") (pin "6") (pinfunction "~{RI}_6") (pintype "input"))
    )
    (net (code "81") (name "unconnected-(IC6-~{RTS}-Pad3)") (class "Default")
      (node (ref "IC6") (pin "3") (pinfunction "~{RTS}_3") (pintype "output"))
    )
    (net (code "82") (name "unconnected-(IC8B-Y0-Pad12)") (class "Default")
      (node (ref "IC8") (pin "12") (pinfunction "Y0_12") (pintype "output"))
    )
    (net (code "83") (name "unconnected-(IC8B-Y1-Pad11)") (class "Default")
      (node (ref "IC8") (pin "11") (pinfunction "Y1_11") (pintype "output"))
    )
    (net (code "84") (name "unconnected-(IC8B-Y2-Pad10)") (class "Default")
      (node (ref "IC8") (pin "10") (pinfunction "Y2_10") (pintype "output"))
    )
    (net (code "85") (name "unconnected-(IC8B-Y3-Pad9)") (class "Default")
      (node (ref "IC8") (pin "9") (pinfunction "Y3_9") (pintype "output"))
    )
    (net (code "86") (name "unconnected-(IC9A-RO-Pad2)") (class "Default")
      (node (ref "IC9") (pin "2") (pinfunction "RO_2") (pintype "output"))
    )
    (net (code "87") (name "unconnected-(IC10A-RO-Pad2)") (class "Default")
      (node (ref "IC10") (pin "2") (pinfunction "RO_2") (pintype "output"))
    )
    (net (code "88") (name "unconnected-(IC12-P$6-Pad6)") (class "Default")
      (node (ref "IC12") (pin "6") (pinfunction "P$6_6") (pintype "bidirectional"))
    )
    (net (code "89") (name "unconnected-(IC13A-ADC6-Pad19)") (class "Default")
      (node (ref "IC13") (pin "19") (pinfunction "ADC6_19") (pintype "passive"))
    )
    (net (code "90") (name "unconnected-(IC13A-ADC7-Pad22)") (class "Default")
      (node (ref "IC13") (pin "22") (pinfunction "ADC7_22") (pintype "passive"))
    )
    (net (code "91") (name "unconnected-(IC13A-PB0(ICP1{slash}CLKO{slash}PCINT0)-Pad12)") (class "Default")
      (node (ref "IC13") (pin "12") (pinfunction "PB0(ICP1/CLKO/PCINT0)_12") (pintype "bidirectional"))
    )
    (net (code "92") (name "unconnected-(IC13A-PB1(OC1A{slash}PCINT1)-Pad13)") (class "Default")
      (node (ref "IC13") (pin "13") (pinfunction "PB1(OC1A/PCINT1)_13") (pintype "bidirectional"))
    )
    (net (code "93") (name "unconnected-(IC13A-PB2(SS{slash}OC1B{slash}PCINT2)-Pad14)") (class "Default")
      (node (ref "IC13") (pin "14") (pinfunction "PB2(SS/OC1B/PCINT2)_14") (pintype "bidirectional"))
    )
    (net (code "94") (name "unconnected-(IC13A-PC5(ADC5{slash}SCL{slash}PCINT13)-Pad28)") (class "Default")
      (node (ref "IC13") (pin "28") (pinfunction "PC5(ADC5/SCL/PCINT13)_28") (pintype "bidirectional"))
    )
    (net (code "95") (name "unconnected-(IC13A-PD4(T0{slash}XCK{slash}PCINT20)-Pad2)") (class "Default")
      (node (ref "IC13") (pin "2") (pinfunction "PD4(T0/XCK/PCINT20)_2") (pintype "bidirectional"))
    )
  )
)
